# IsoBunny.net
KiCad netlist of a schematic drawn in EAGLE
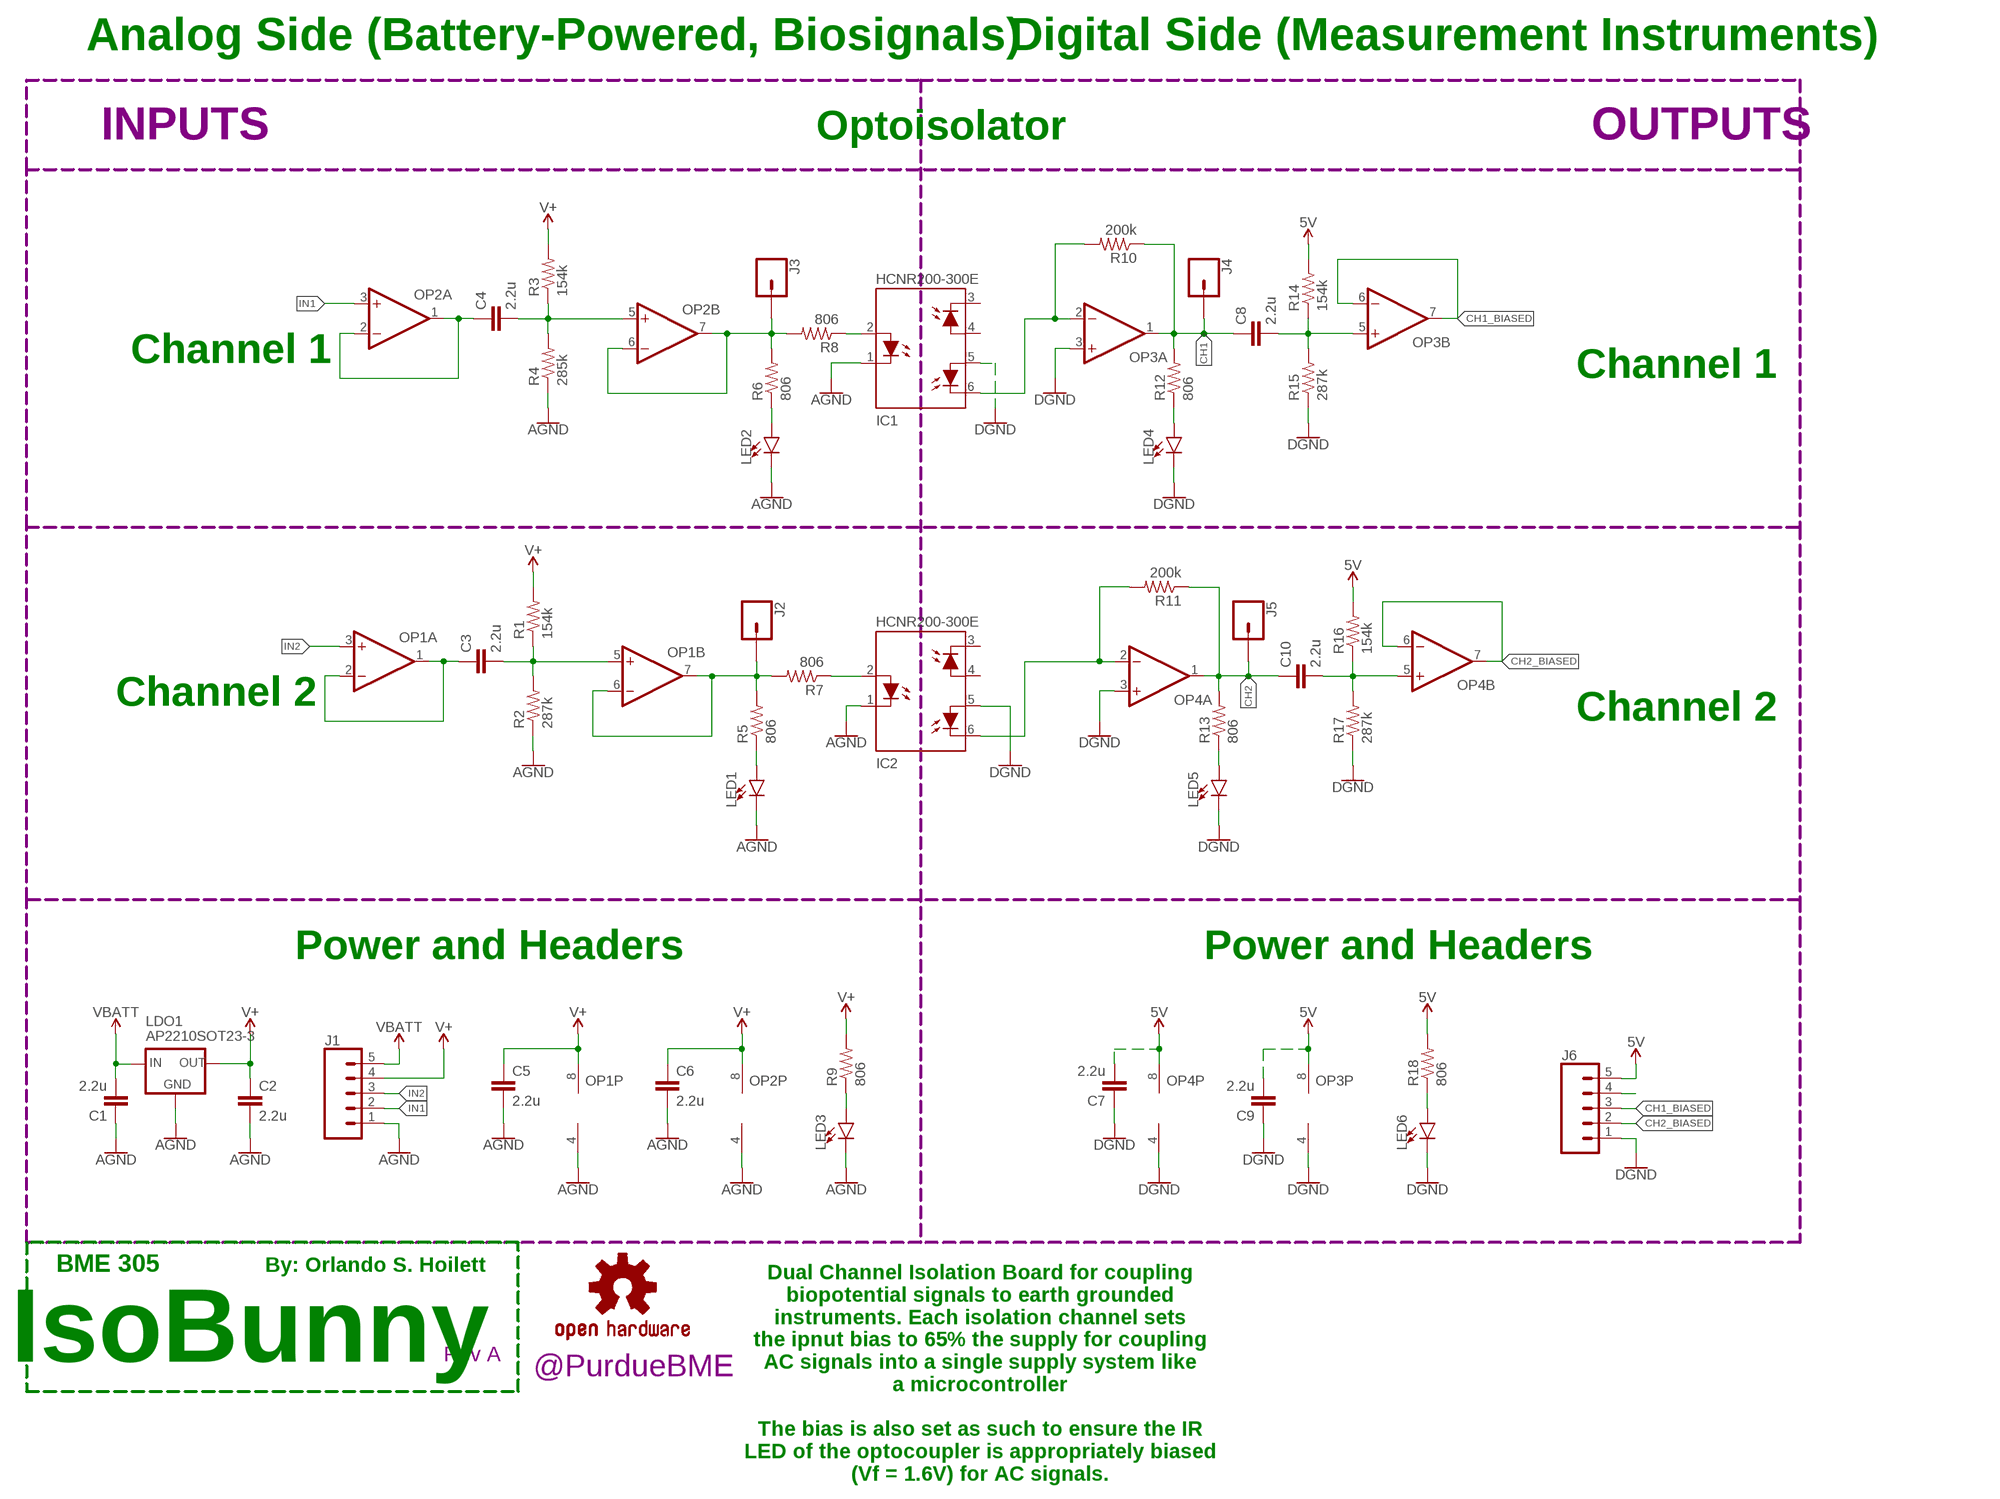
[diagram p0: schematic, sheet 1]

(export (version "E")
  (design (tool "Eeschema 10.0.6"))
  (components
    (comp (ref "C1")
      (value "2.2u")
      (footprint "eagle-import:C0603")
      (libsource (lib "eagle-import") (part "CAPACITOR0603"))
    )
    (comp (ref "C2")
      (value "2.2u")
      (footprint "eagle-import:C0603")
      (libsource (lib "eagle-import") (part "CAPACITOR0603"))
    )
    (comp (ref "C3")
      (value "2.2u")
      (footprint "eagle-import:C0603")
      (libsource (lib "eagle-import") (part "CAPACITOR0603"))
    )
    (comp (ref "C4")
      (value "2.2u")
      (footprint "eagle-import:C0603")
      (libsource (lib "eagle-import") (part "CAPACITOR0603"))
    )
    (comp (ref "C5")
      (value "2.2u")
      (footprint "eagle-import:C0603")
      (libsource (lib "eagle-import") (part "CAPACITOR0603"))
    )
    (comp (ref "C6")
      (value "2.2u")
      (footprint "eagle-import:C0603")
      (libsource (lib "eagle-import") (part "CAPACITOR0603"))
    )
    (comp (ref "C7")
      (value "2.2u")
      (footprint "eagle-import:C0603")
      (libsource (lib "eagle-import") (part "CAPACITOR0603"))
    )
    (comp (ref "C8")
      (value "2.2u")
      (footprint "eagle-import:C0603")
      (libsource (lib "eagle-import") (part "CAPACITOR0603"))
    )
    (comp (ref "C9")
      (value "2.2u")
      (footprint "eagle-import:C0603")
      (libsource (lib "eagle-import") (part "CAPACITOR0603"))
    )
    (comp (ref "C10")
      (value "2.2u")
      (footprint "eagle-import:C0603")
      (libsource (lib "eagle-import") (part "CAPACITOR0603"))
    )
    (comp (ref "IC1")
      (value "HCNR200-300E")
      (footprint "eagle-import:DIP8-400")
      (libsource (lib "eagle-import") (part "HCNR20-300E0"))
    )
    (comp (ref "IC2")
      (value "HCNR200-300E")
      (footprint "eagle-import:DIP8-400")
      (libsource (lib "eagle-import") (part "HCNR20-300E0"))
    )
    (comp (ref "J1")
      (value "CONN_05")
      (footprint "eagle-import:1X05")
      (libsource (lib "eagle-import") (part "CONN_05"))
    )
    (comp (ref "J2")
      (value "CONN_01PTH_NO_SILK_KIT")
      (footprint "eagle-import:1X01NS_KIT")
      (libsource (lib "eagle-import") (part "CONN_01PTH_NO_SILK_KIT"))
    )
    (comp (ref "J3")
      (value "CONN_01PTH_NO_SILK_KIT")
      (footprint "eagle-import:1X01NS_KIT")
      (libsource (lib "eagle-import") (part "CONN_01PTH_NO_SILK_KIT"))
    )
    (comp (ref "J4")
      (value "CONN_01PTH_NO_SILK_KIT")
      (footprint "eagle-import:1X01NS_KIT")
      (libsource (lib "eagle-import") (part "CONN_01PTH_NO_SILK_KIT"))
    )
    (comp (ref "J5")
      (value "CONN_01PTH_NO_SILK_KIT")
      (footprint "eagle-import:1X01NS_KIT")
      (libsource (lib "eagle-import") (part "CONN_01PTH_NO_SILK_KIT"))
    )
    (comp (ref "J6")
      (value "CONN_05")
      (footprint "eagle-import:1X05")
      (libsource (lib "eagle-import") (part "CONN_05"))
    )
    (comp (ref "LDO1")
      (value "AP2210SOT23-3")
      (footprint "eagle-import:SOT23")
      (libsource (lib "eagle-import") (part "AP2210SOT23-3"))
    )
    (comp (ref "LED1")
      (value "LED5MM")
      (footprint "eagle-import:LED_5MM")
      (libsource (lib "eagle-import") (part "LED5MM"))
    )
    (comp (ref "LED2")
      (value "LED5MM")
      (footprint "eagle-import:LED_5MM")
      (libsource (lib "eagle-import") (part "LED5MM"))
    )
    (comp (ref "LED3")
      (value "LED5MM")
      (footprint "eagle-import:LED_5MM")
      (libsource (lib "eagle-import") (part "LED5MM"))
    )
    (comp (ref "LED4")
      (value "LED5MM")
      (footprint "eagle-import:LED_5MM")
      (libsource (lib "eagle-import") (part "LED5MM"))
    )
    (comp (ref "LED5")
      (value "LED5MM")
      (footprint "eagle-import:LED_5MM")
      (libsource (lib "eagle-import") (part "LED5MM"))
    )
    (comp (ref "LED6")
      (value "LED5MM")
      (footprint "eagle-import:LED_5MM")
      (libsource (lib "eagle-import") (part "LED5MM"))
    )
    (comp (ref "LOGO1")
      (value "OSHW-LOGOL")
      (footprint "eagle-import:OSHW-LOGO-L")
      (libsource (lib "eagle-import") (part "OSHW-LOGOL"))
    )
    (comp (ref "OP1")
      (value "OP-DUALR")
      (footprint "eagle-import:SO8")
      (fields (field (name "MPN") "AD8607ARMZ-R2"))
      (libsource (lib "eagle-import") (part "OP-DUALR"))
    )
    (comp (ref "OP2")
      (value "OP-DUALR")
      (footprint "eagle-import:SO8")
      (fields (field (name "MPN") "AD8607ARMZ-R2"))
      (libsource (lib "eagle-import") (part "OP-DUALR"))
    )
    (comp (ref "OP3")
      (value "OP-DUALR")
      (footprint "eagle-import:SO8")
      (fields (field (name "MPN") "AD8607ARMZ-R2"))
      (libsource (lib "eagle-import") (part "OP-DUALR"))
    )
    (comp (ref "OP4")
      (value "OP-DUALR")
      (footprint "eagle-import:SO8")
      (fields (field (name "MPN") "AD8607ARMZ-R2"))
      (libsource (lib "eagle-import") (part "OP-DUALR"))
    )
    (comp (ref "R1")
      (value "154k")
      (footprint "eagle-import:R0603")
      (libsource (lib "eagle-import") (part "RESISTOR0603"))
    )
    (comp (ref "R2")
      (value "287k")
      (footprint "eagle-import:R0603")
      (libsource (lib "eagle-import") (part "RESISTOR0603"))
    )
    (comp (ref "R3")
      (value "154k")
      (footprint "eagle-import:R0603")
      (libsource (lib "eagle-import") (part "RESISTOR0603"))
    )
    (comp (ref "R4")
      (value "285k")
      (footprint "eagle-import:R0603")
      (libsource (lib "eagle-import") (part "RESISTOR0603"))
    )
    (comp (ref "R5")
      (value "806")
      (footprint "eagle-import:R0603")
      (libsource (lib "eagle-import") (part "RESISTOR0603"))
    )
    (comp (ref "R6")
      (value "806")
      (footprint "eagle-import:R0603")
      (libsource (lib "eagle-import") (part "RESISTOR0603"))
    )
    (comp (ref "R7")
      (value "806")
      (footprint "eagle-import:R0603")
      (libsource (lib "eagle-import") (part "RESISTOR0603"))
    )
    (comp (ref "R8")
      (value "806")
      (footprint "eagle-import:R0603")
      (libsource (lib "eagle-import") (part "RESISTOR0603"))
    )
    (comp (ref "R9")
      (value "806")
      (footprint "eagle-import:R0603")
      (libsource (lib "eagle-import") (part "RESISTOR0603"))
    )
    (comp (ref "R10")
      (value "200k")
      (footprint "eagle-import:R0603")
      (libsource (lib "eagle-import") (part "RESISTOR0603"))
    )
    (comp (ref "R11")
      (value "200k")
      (footprint "eagle-import:R0603")
      (libsource (lib "eagle-import") (part "RESISTOR0603"))
    )
    (comp (ref "R12")
      (value "806")
      (footprint "eagle-import:R0603")
      (libsource (lib "eagle-import") (part "RESISTOR0603"))
    )
    (comp (ref "R13")
      (value "806")
      (footprint "eagle-import:R0603")
      (libsource (lib "eagle-import") (part "RESISTOR0603"))
    )
    (comp (ref "R14")
      (value "154k")
      (footprint "eagle-import:R0603")
      (libsource (lib "eagle-import") (part "RESISTOR0603"))
    )
    (comp (ref "R15")
      (value "287k")
      (footprint "eagle-import:R0603")
      (libsource (lib "eagle-import") (part "RESISTOR0603"))
    )
    (comp (ref "R16")
      (value "154k")
      (footprint "eagle-import:R0603")
      (libsource (lib "eagle-import") (part "RESISTOR0603"))
    )
    (comp (ref "R17")
      (value "287k")
      (footprint "eagle-import:R0603")
      (libsource (lib "eagle-import") (part "RESISTOR0603"))
    )
    (comp (ref "R18")
      (value "806")
      (footprint "eagle-import:R0603")
      (libsource (lib "eagle-import") (part "RESISTOR0603"))
    )
    (comp (ref "REV1")
      (value "REVISION.A")
      (footprint "eagle-import:REV.A")
      (libsource (lib "eagle-import") (part "REVISION.A"))
    )
    (comp (ref "U$1")
      (value "PURDUE_BME_HANDLE")
      (footprint "eagle-import:PURDUE_BME_HANDLE.1")
      (libsource (lib "eagle-import") (part "PURDUE_BME_HANDLE"))
    )
  )
  (nets
    (net (code "1") (name "5V") (class "Default")
      (node (ref "C7") (pin "2") (pinfunction "2_2") (pintype "passive"))
      (node (ref "C9") (pin "2") (pinfunction "2_2") (pintype "passive"))
      (node (ref "J6") (pin "5") (pinfunction "5_5") (pintype "passive"))
      (node (ref "OP3") (pin "8") (pinfunction "V+_8") (pintype "power_in"))
      (node (ref "OP4") (pin "8") (pinfunction "V+_8") (pintype "power_in"))
      (node (ref "R14") (pin "2") (pinfunction "2_2") (pintype "passive"))
      (node (ref "R16") (pin "2") (pinfunction "2_2") (pintype "passive"))
      (node (ref "R18") (pin "2") (pinfunction "2_2") (pintype "passive"))
    )
    (net (code "2") (name "AGND") (class "Default")
      (node (ref "C1") (pin "1") (pinfunction "1_1") (pintype "passive"))
      (node (ref "C2") (pin "2") (pinfunction "2_2") (pintype "passive"))
      (node (ref "C5") (pin "2") (pinfunction "2_2") (pintype "passive"))
      (node (ref "C6") (pin "2") (pinfunction "2_2") (pintype "passive"))
      (node (ref "IC1") (pin "1") (pinfunction "C_1") (pintype "passive"))
      (node (ref "IC2") (pin "1") (pinfunction "C_1") (pintype "passive"))
      (node (ref "J1") (pin "1") (pinfunction "1_1") (pintype "passive"))
      (node (ref "LDO1") (pin "1") (pinfunction "GND_1") (pintype "input"))
      (node (ref "LED1") (pin "K") (pinfunction "C_K") (pintype "passive"))
      (node (ref "LED2") (pin "K") (pinfunction "C_K") (pintype "passive"))
      (node (ref "LED3") (pin "K") (pinfunction "C_K") (pintype "passive"))
      (node (ref "OP1") (pin "4") (pinfunction "V-_4") (pintype "power_in"))
      (node (ref "OP2") (pin "4") (pinfunction "V-_4") (pintype "power_in"))
      (node (ref "R2") (pin "1") (pinfunction "1_1") (pintype "passive"))
      (node (ref "R4") (pin "1") (pinfunction "1_1") (pintype "passive"))
    )
    (net (code "3") (name "CH1") (class "Default")
      (node (ref "C8") (pin "1") (pinfunction "1_1") (pintype "passive"))
      (node (ref "J4") (pin "1") (pinfunction "1_1") (pintype "passive"))
      (node (ref "OP3") (pin "1") (pinfunction "OUT_1") (pintype "output"))
      (node (ref "R10") (pin "1") (pinfunction "1_1") (pintype "passive"))
      (node (ref "R12") (pin "2") (pinfunction "2_2") (pintype "passive"))
    )
    (net (code "4") (name "CH1_BIASED") (class "Default")
      (node (ref "J6") (pin "3") (pinfunction "3_3") (pintype "passive"))
      (node (ref "OP3") (pin "6") (pinfunction "-IN_6") (pintype "input"))
      (node (ref "OP3") (pin "7") (pinfunction "OUT_7") (pintype "output"))
    )
    (net (code "5") (name "CH2") (class "Default")
      (node (ref "C10") (pin "1") (pinfunction "1_1") (pintype "passive"))
      (node (ref "J5") (pin "1") (pinfunction "1_1") (pintype "passive"))
      (node (ref "OP4") (pin "1") (pinfunction "OUT_1") (pintype "output"))
      (node (ref "R11") (pin "1") (pinfunction "1_1") (pintype "passive"))
      (node (ref "R13") (pin "2") (pinfunction "2_2") (pintype "passive"))
    )
    (net (code "6") (name "CH2_BIASED") (class "Default")
      (node (ref "J6") (pin "2") (pinfunction "2_2") (pintype "passive"))
      (node (ref "OP4") (pin "6") (pinfunction "-IN_6") (pintype "input"))
      (node (ref "OP4") (pin "7") (pinfunction "OUT_7") (pintype "output"))
    )
    (net (code "7") (name "DGND") (class "Default")
      (node (ref "C7") (pin "1") (pinfunction "1_1") (pintype "passive"))
      (node (ref "C9") (pin "1") (pinfunction "1_1") (pintype "passive"))
      (node (ref "IC1") (pin "5") (pinfunction "A2_5") (pintype "passive"))
      (node (ref "IC2") (pin "5") (pinfunction "A2_5") (pintype "passive"))
      (node (ref "J6") (pin "1") (pinfunction "1_1") (pintype "passive"))
      (node (ref "LED4") (pin "K") (pinfunction "C_K") (pintype "passive"))
      (node (ref "LED5") (pin "K") (pinfunction "C_K") (pintype "passive"))
      (node (ref "LED6") (pin "K") (pinfunction "C_K") (pintype "passive"))
      (node (ref "OP3") (pin "3") (pinfunction "+IN_3") (pintype "input"))
      (node (ref "OP3") (pin "4") (pinfunction "V-_4") (pintype "power_in"))
      (node (ref "OP4") (pin "3") (pinfunction "+IN_3") (pintype "input"))
      (node (ref "OP4") (pin "4") (pinfunction "V-_4") (pintype "power_in"))
      (node (ref "R15") (pin "1") (pinfunction "1_1") (pintype "passive"))
      (node (ref "R17") (pin "1") (pinfunction "1_1") (pintype "passive"))
    )
    (net (code "8") (name "IN1") (class "Default")
      (node (ref "J1") (pin "2") (pinfunction "2_2") (pintype "passive"))
      (node (ref "OP2") (pin "3") (pinfunction "+IN_3") (pintype "input"))
    )
    (net (code "9") (name "IN2") (class "Default")
      (node (ref "J1") (pin "3") (pinfunction "3_3") (pintype "passive"))
      (node (ref "OP1") (pin "3") (pinfunction "+IN_3") (pintype "input"))
    )
    (net (code "10") (name "Net-(IC1-A)") (class "Default")
      (node (ref "IC1") (pin "2") (pinfunction "A_2") (pintype "passive"))
      (node (ref "R8") (pin "1") (pinfunction "1_1") (pintype "passive"))
    )
    (net (code "11") (name "Net-(IC1-C2)") (class "Default")
      (node (ref "IC1") (pin "6") (pinfunction "C2_6") (pintype "passive"))
      (node (ref "OP3") (pin "2") (pinfunction "-IN_2") (pintype "input"))
      (node (ref "R10") (pin "2") (pinfunction "2_2") (pintype "passive"))
    )
    (net (code "12") (name "Net-(IC2-A)") (class "Default")
      (node (ref "IC2") (pin "2") (pinfunction "A_2") (pintype "passive"))
      (node (ref "R7") (pin "1") (pinfunction "1_1") (pintype "passive"))
    )
    (net (code "13") (name "Net-(IC2-C2)") (class "Default")
      (node (ref "IC2") (pin "6") (pinfunction "C2_6") (pintype "passive"))
      (node (ref "OP4") (pin "2") (pinfunction "-IN_2") (pintype "input"))
      (node (ref "R11") (pin "2") (pinfunction "2_2") (pintype "passive"))
    )
    (net (code "14") (name "Net-(LED1-PadA)") (class "Default")
      (node (ref "LED1") (pin "A") (pinfunction "A_A") (pintype "passive"))
      (node (ref "R5") (pin "1") (pinfunction "1_1") (pintype "passive"))
    )
    (net (code "15") (name "Net-(LED2-PadA)") (class "Default")
      (node (ref "LED2") (pin "A") (pinfunction "A_A") (pintype "passive"))
      (node (ref "R6") (pin "1") (pinfunction "1_1") (pintype "passive"))
    )
    (net (code "16") (name "Net-(LED3-PadA)") (class "Default")
      (node (ref "LED3") (pin "A") (pinfunction "A_A") (pintype "passive"))
      (node (ref "R9") (pin "1") (pinfunction "1_1") (pintype "passive"))
    )
    (net (code "17") (name "Net-(LED4-PadA)") (class "Default")
      (node (ref "LED4") (pin "A") (pinfunction "A_A") (pintype "passive"))
      (node (ref "R12") (pin "1") (pinfunction "1_1") (pintype "passive"))
    )
    (net (code "18") (name "Net-(LED5-PadA)") (class "Default")
      (node (ref "LED5") (pin "A") (pinfunction "A_A") (pintype "passive"))
      (node (ref "R13") (pin "1") (pinfunction "1_1") (pintype "passive"))
    )
    (net (code "19") (name "Net-(LED6-PadA)") (class "Default")
      (node (ref "LED6") (pin "A") (pinfunction "A_A") (pintype "passive"))
      (node (ref "R18") (pin "1") (pinfunction "1_1") (pintype "passive"))
    )
    (net (code "20") (name "Net-(OP1A--IN)") (class "Default")
      (node (ref "C3") (pin "1") (pinfunction "1_1") (pintype "passive"))
      (node (ref "OP1") (pin "1") (pinfunction "OUT_1") (pintype "output"))
      (node (ref "OP1") (pin "2") (pinfunction "-IN_2") (pintype "input"))
    )
    (net (code "21") (name "Net-(OP1B-+IN)") (class "Default")
      (node (ref "C3") (pin "2") (pinfunction "2_2") (pintype "passive"))
      (node (ref "OP1") (pin "5") (pinfunction "+IN_5") (pintype "input"))
      (node (ref "R1") (pin "1") (pinfunction "1_1") (pintype "passive"))
      (node (ref "R2") (pin "2") (pinfunction "2_2") (pintype "passive"))
    )
    (net (code "22") (name "Net-(OP1B--IN)") (class "Default")
      (node (ref "J2") (pin "1") (pinfunction "1_1") (pintype "passive"))
      (node (ref "OP1") (pin "6") (pinfunction "-IN_6") (pintype "input"))
      (node (ref "OP1") (pin "7") (pinfunction "OUT_7") (pintype "output"))
      (node (ref "R5") (pin "2") (pinfunction "2_2") (pintype "passive"))
      (node (ref "R7") (pin "2") (pinfunction "2_2") (pintype "passive"))
    )
    (net (code "23") (name "Net-(OP2A--IN)") (class "Default")
      (node (ref "C4") (pin "1") (pinfunction "1_1") (pintype "passive"))
      (node (ref "OP2") (pin "1") (pinfunction "OUT_1") (pintype "output"))
      (node (ref "OP2") (pin "2") (pinfunction "-IN_2") (pintype "input"))
    )
    (net (code "24") (name "Net-(OP2B-+IN)") (class "Default")
      (node (ref "C4") (pin "2") (pinfunction "2_2") (pintype "passive"))
      (node (ref "OP2") (pin "5") (pinfunction "+IN_5") (pintype "input"))
      (node (ref "R3") (pin "1") (pinfunction "1_1") (pintype "passive"))
      (node (ref "R4") (pin "2") (pinfunction "2_2") (pintype "passive"))
    )
    (net (code "25") (name "Net-(OP2B--IN)") (class "Default")
      (node (ref "J3") (pin "1") (pinfunction "1_1") (pintype "passive"))
      (node (ref "OP2") (pin "6") (pinfunction "-IN_6") (pintype "input"))
      (node (ref "OP2") (pin "7") (pinfunction "OUT_7") (pintype "output"))
      (node (ref "R6") (pin "2") (pinfunction "2_2") (pintype "passive"))
      (node (ref "R8") (pin "2") (pinfunction "2_2") (pintype "passive"))
    )
    (net (code "26") (name "Net-(OP3B-+IN)") (class "Default")
      (node (ref "C8") (pin "2") (pinfunction "2_2") (pintype "passive"))
      (node (ref "OP3") (pin "5") (pinfunction "+IN_5") (pintype "input"))
      (node (ref "R14") (pin "1") (pinfunction "1_1") (pintype "passive"))
      (node (ref "R15") (pin "2") (pinfunction "2_2") (pintype "passive"))
    )
    (net (code "27") (name "Net-(OP4B-+IN)") (class "Default")
      (node (ref "C10") (pin "2") (pinfunction "2_2") (pintype "passive"))
      (node (ref "OP4") (pin "5") (pinfunction "+IN_5") (pintype "input"))
      (node (ref "R16") (pin "1") (pinfunction "1_1") (pintype "passive"))
      (node (ref "R17") (pin "2") (pinfunction "2_2") (pintype "passive"))
    )
    (net (code "28") (name "V+") (class "Default")
      (node (ref "C2") (pin "1") (pinfunction "1_1") (pintype "passive"))
      (node (ref "C5") (pin "1") (pinfunction "1_1") (pintype "passive"))
      (node (ref "C6") (pin "1") (pinfunction "1_1") (pintype "passive"))
      (node (ref "J1") (pin "4") (pinfunction "4_4") (pintype "passive"))
      (node (ref "LDO1") (pin "2") (pinfunction "OUT_2") (pintype "passive"))
      (node (ref "OP1") (pin "8") (pinfunction "V+_8") (pintype "power_in"))
      (node (ref "OP2") (pin "8") (pinfunction "V+_8") (pintype "power_in"))
      (node (ref "R1") (pin "2") (pinfunction "2_2") (pintype "passive"))
      (node (ref "R3") (pin "2") (pinfunction "2_2") (pintype "passive"))
      (node (ref "R9") (pin "2") (pinfunction "2_2") (pintype "passive"))
    )
    (net (code "29") (name "VBATT") (class "Default")
      (node (ref "C1") (pin "2") (pinfunction "2_2") (pintype "passive"))
      (node (ref "J1") (pin "5") (pinfunction "5_5") (pintype "passive"))
      (node (ref "LDO1") (pin "3") (pinfunction "IN_3") (pintype "input"))
    )
    (net (code "30") (name "unconnected-(IC1-A1-Pad4)") (class "Default")
      (node (ref "IC1") (pin "4") (pinfunction "A1_4") (pintype "passive"))
    )
    (net (code "31") (name "unconnected-(IC1-C1-Pad3)") (class "Default")
      (node (ref "IC1") (pin "3") (pinfunction "C1_3") (pintype "passive"))
    )
    (net (code "32") (name "unconnected-(IC2-A1-Pad4)") (class "Default")
      (node (ref "IC2") (pin "4") (pinfunction "A1_4") (pintype "passive"))
    )
    (net (code "33") (name "unconnected-(IC2-C1-Pad3)") (class "Default")
      (node (ref "IC2") (pin "3") (pinfunction "C1_3") (pintype "passive"))
    )
    (net (code "34") (name "unconnected-(J6-Pad4)") (class "Default")
      (node (ref "J6") (pin "4") (pinfunction "4_4") (pintype "passive"))
    )
  )
)
